# Power.net
KiCad netlist of a schematic drawn in Altium Designer
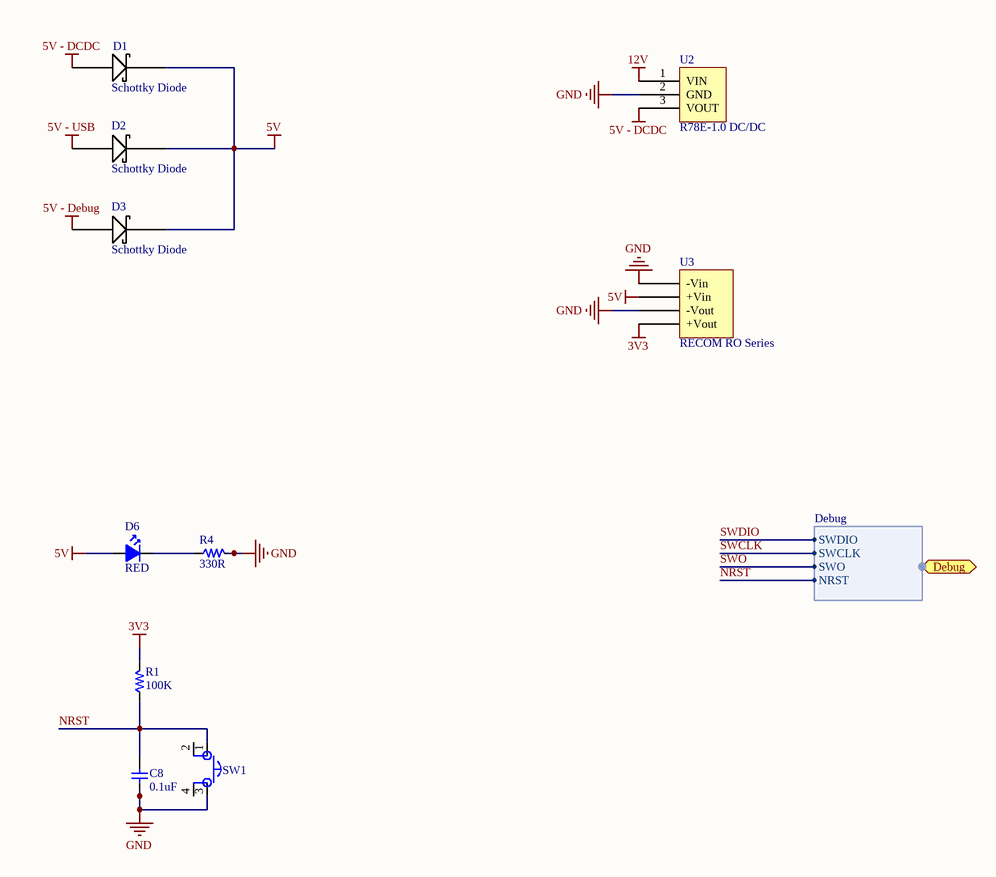
[diagram p0: Power.SchDoc]

(export (version "E")
  (design (tool "Eeschema 10.0.6"))
  (components
    (comp (ref "C8")
      (value "0.1uF")
      (footprint "PCB_GENERIC_SMD_0603")
      (description "CAP CER 0603 0.1uF 16V X5R 20%")
      (fields (field (name "TOLERANCE") "20%") (field (name "VOLTAGE") "16V"))
      (libsource (lib "CAP-0603") (part "C060-000U1-00"))
    )
    (comp (ref "D1")
      (value "Schottky Diode")
      (footprint "ON Semi Schottky Diode - MBRM110LT1G")
      (libsource (lib "ON Semi Schottky Diode - MBRM110LT1G") (part "ON Semi Schottky Diode - MBRM110LT1G"))
    )
    (comp (ref "D2")
      (value "Schottky Diode")
      (footprint "ON Semi Schottky Diode - MBRM110LT1G")
      (libsource (lib "ON Semi Schottky Diode - MBRM110LT1G") (part "ON Semi Schottky Diode - MBRM110LT1G"))
    )
    (comp (ref "D3")
      (value "Schottky Diode")
      (footprint "ON Semi Schottky Diode - MBRM110LT1G")
      (libsource (lib "ON Semi Schottky Diode - MBRM110LT1G") (part "ON Semi Schottky Diode - MBRM110LT1G"))
    )
    (comp (ref "D6")
      (value "D060-000R2-00")
      (footprint "SMD_0603_LED")
      (description "LED 0603 RED 2Vf 20mA")
      (fields (field (name "COLOR") "RED"))
      (libsource (lib "LED-0603") (part "D060-000R2-00"))
    )
    (comp (ref "R1")
      (value "100K")
      (footprint "PCB_GENERIC_SMD_0603")
      (description "RES 0603 100K 5% 63mW")
      (fields (field (name "TOLERANCE") "5%") (field (name "POWER") "63mW"))
      (libsource (lib "RES-0603") (part "R060-00104-05"))
    )
    (comp (ref "R4")
      (value "330R")
      (footprint "PCB_GENERIC_SMD_0603")
      (description "RES 0603 330ohm 5% 63mW")
      (fields (field (name "TOLERANCE") "5%") (field (name "POWER") "63mW"))
      (libsource (lib "RES-0603") (part "R060-00331-05"))
    )
    (comp (ref "SW1")
      (value "Tactile Switch")
      (footprint "C&K 4 pin Tactile Switch")
      (libsource (lib "C&K 4 Pin Tactile Switch") (part "C&K Tactile Switch"))
    )
    (comp (ref "U2")
      (value "R78E-1.0 DC/DC")
      (footprint "R78-1.0")
      (libsource (lib "R78E-1.0_DCDC_SCH") (part "R78E-1.0"))
    )
    (comp (ref "U3")
      (value "RECOM RO Series")
      (footprint "RECOM RO Series 1W DCDC")
      (libsource (lib "RECOM RO Series 1W DCDC") (part "RECOM RO Series DCDC Converter"))
    )
  )
  (nets
    (net (code "2") (name "/NRST") (class "Default")
      (node (ref "C8") (pin "2") (pinfunction "2_2") (pintype "passive"))
      (node (ref "R1") (pin "1") (pinfunction "1_1") (pintype "passive"))
      (node (ref "SW1") (pin "1") (pinfunction "1_1") (pintype "passive"))
    )
    (net (code "7") (name "3V3") (class "Default")
      (node (ref "R1") (pin "2") (pinfunction "2_2") (pintype "passive"))
      (node (ref "U3") (pin "4") (pinfunction "+Vout_4") (pintype "passive"))
    )
    (net (code "8") (name "5V") (class "Default")
      (node (ref "D1") (pin "1") (pinfunction "1_1") (pintype "passive"))
      (node (ref "D2") (pin "1") (pinfunction "1_1") (pintype "passive"))
      (node (ref "D3") (pin "1") (pinfunction "1_1") (pintype "passive"))
      (node (ref "D6") (pin "2") (pinfunction "A_2") (pintype "passive"))
      (node (ref "U3") (pin "2") (pinfunction "+Vin_2") (pintype "passive"))
    )
    (net (code "9") (name "5V - DCDC") (class "Default")
      (node (ref "D1") (pin "2") (pinfunction "2_2") (pintype "passive"))
      (node (ref "U2") (pin "3") (pinfunction "VOUT_3") (pintype "passive"))
    )
    (net (code "10") (name "5V - Debug") (class "Default")
      (node (ref "D3") (pin "2") (pinfunction "2_2") (pintype "passive"))
    )
    (net (code "11") (name "5V - USB") (class "Default")
      (node (ref "D2") (pin "2") (pinfunction "2_2") (pintype "passive"))
    )
    (net (code "12") (name "12V") (class "Default")
      (node (ref "U2") (pin "1") (pinfunction "VIN_1") (pintype "passive"))
    )
    (net (code "13") (name "GND") (class "Default")
      (node (ref "C8") (pin "1") (pinfunction "1_1") (pintype "passive"))
      (node (ref "R4") (pin "2") (pinfunction "2_2") (pintype "passive"))
      (node (ref "SW1") (pin "3") (pinfunction "3_3") (pintype "passive"))
      (node (ref "U2") (pin "2") (pinfunction "GND_2") (pintype "passive"))
      (node (ref "U3") (pin "1") (pinfunction "-Vin_1") (pintype "passive"))
      (node (ref "U3") (pin "3") (pinfunction "-Vout_3") (pintype "passive"))
    )
    (net (code "14") (name "Net-(D6-K)") (class "Default")
      (node (ref "D6") (pin "1") (pinfunction "K_1") (pintype "passive"))
      (node (ref "R4") (pin "1") (pinfunction "1_1") (pintype "passive"))
    )
    (net (code "15") (name "unconnected-(SW1-Pad2)") (class "Default")
      (node (ref "SW1") (pin "2") (pinfunction "2_2") (pintype "passive"))
    )
    (net (code "16") (name "unconnected-(SW1-Pad4)") (class "Default")
      (node (ref "SW1") (pin "4") (pinfunction "4_4") (pintype "passive"))
    )
  )
)
